# MAIN-MODULE.net
KiCad netlist of a schematic drawn in Altium Designer
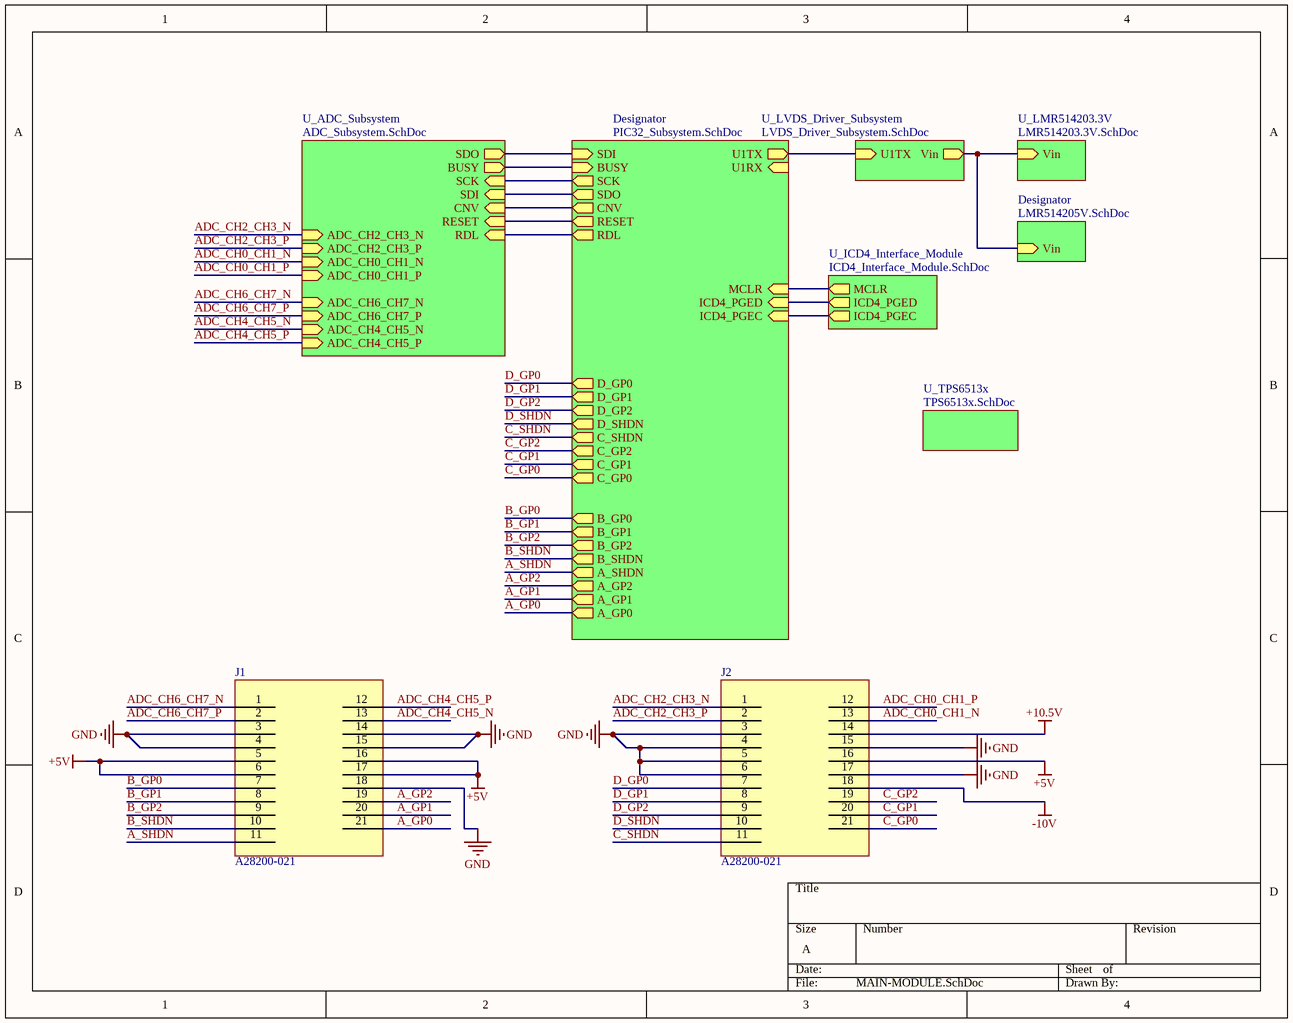
[diagram p0: MAIN-MODULE.SchDoc]

(export (version "E")
  (design (tool "Eeschema 10.0.6"))
  (components
    (comp (ref "J1")
      (value "A28200-021")
      (footprint "A28200-021")
      (description "CONN NANO-D PLUG 21POS SMD SLDR")
      (libsource (lib "Connectors") (part "A28200-021"))
    )
    (comp (ref "J2")
      (value "A28200-021")
      (footprint "A28200-021")
      (description "CONN NANO-D PLUG 21POS SMD SLDR")
      (libsource (lib "Connectors") (part "A28200-021"))
    )
  )
  (nets
    (net (code "1") (name "+5V") (class "Default")
      (node (ref "J1") (pin "16") (pintype "passive"))
      (node (ref "J1") (pin "17") (pintype "passive"))
      (node (ref "J1") (pin "5") (pintype "passive"))
      (node (ref "J1") (pin "6") (pintype "passive"))
      (node (ref "J2") (pin "16") (pintype "passive"))
    )
    (net (code "2") (name "+10.5V") (class "Default") (node (ref "J2") (pin "14") (pintype "passive")))
    (net (code "3") (name "-10V") (class "Default") (node (ref "J2") (pin "18") (pintype "passive")))
    (net (code "4") (name "/ADC_CH0_CH1_N") (class "Default")
      (node (ref "J2") (pin "13") (pintype "passive"))
    )
    (net (code "5") (name "/ADC_CH0_CH1_P") (class "Default")
      (node (ref "J2") (pin "12") (pintype "passive"))
    )
    (net (code "6") (name "/ADC_CH2_CH3_N") (class "Default") (node (ref "J2") (pin "1") (pintype "passive")))
    (net (code "7") (name "/ADC_CH2_CH3_P") (class "Default") (node (ref "J2") (pin "2") (pintype "passive")))
    (net (code "8") (name "/ADC_CH4_CH5_N") (class "Default")
      (node (ref "J1") (pin "13") (pintype "passive"))
    )
    (net (code "9") (name "/ADC_CH4_CH5_P") (class "Default")
      (node (ref "J1") (pin "12") (pintype "passive"))
    )
    (net (code "10") (name "/ADC_CH6_CH7_N") (class "Default")
      (node (ref "J1") (pin "1") (pintype "passive"))
    )
    (net (code "11") (name "/ADC_CH6_CH7_P") (class "Default")
      (node (ref "J1") (pin "2") (pintype "passive"))
    )
    (net (code "12") (name "/A_GP0") (class "Default") (node (ref "J1") (pin "21") (pintype "passive")))
    (net (code "13") (name "/A_GP1") (class "Default") (node (ref "J1") (pin "20") (pintype "passive")))
    (net (code "14") (name "/A_GP2") (class "Default") (node (ref "J1") (pin "19") (pintype "passive")))
    (net (code "15") (name "/A_SHDN") (class "Default") (node (ref "J1") (pin "11") (pintype "passive")))
    (net (code "17") (name "/B_GP0") (class "Default") (node (ref "J1") (pin "7") (pintype "passive")))
    (net (code "18") (name "/B_GP1") (class "Default") (node (ref "J1") (pin "8") (pintype "passive")))
    (net (code "19") (name "/B_GP2") (class "Default") (node (ref "J1") (pin "9") (pintype "passive")))
    (net (code "20") (name "/B_SHDN") (class "Default") (node (ref "J1") (pin "10") (pintype "passive")))
    (net (code "22") (name "/C_GP0") (class "Default") (node (ref "J2") (pin "21") (pintype "passive")))
    (net (code "23") (name "/C_GP1") (class "Default") (node (ref "J2") (pin "20") (pintype "passive")))
    (net (code "24") (name "/C_GP2") (class "Default") (node (ref "J2") (pin "19") (pintype "passive")))
    (net (code "25") (name "/C_SHDN") (class "Default") (node (ref "J2") (pin "11") (pintype "passive")))
    (net (code "26") (name "/D_GP0") (class "Default") (node (ref "J2") (pin "7") (pintype "passive")))
    (net (code "27") (name "/D_GP1") (class "Default") (node (ref "J2") (pin "8") (pintype "passive")))
    (net (code "28") (name "/D_GP2") (class "Default") (node (ref "J2") (pin "9") (pintype "passive")))
    (net (code "29") (name "/D_SHDN") (class "Default") (node (ref "J2") (pin "10") (pintype "passive")))
    (net (code "41") (name "GND") (class "Default")
      (node (ref "J1") (pin "14") (pintype "passive"))
      (node (ref "J1") (pin "15") (pintype "passive"))
      (node (ref "J1") (pin "18") (pintype "passive"))
      (node (ref "J1") (pin "3") (pintype "passive"))
      (node (ref "J1") (pin "4") (pintype "passive"))
      (node (ref "J2") (pin "15") (pintype "passive"))
      (node (ref "J2") (pin "17") (pintype "passive"))
      (node (ref "J2") (pin "3") (pintype "passive"))
      (node (ref "J2") (pin "4") (pintype "passive"))
      (node (ref "J2") (pin "5") (pintype "passive"))
      (node (ref "J2") (pin "6") (pintype "passive"))
    )
  )
)
